# ft231x-breakout-v11.net
KiCad netlist of a schematic drawn in EAGLE
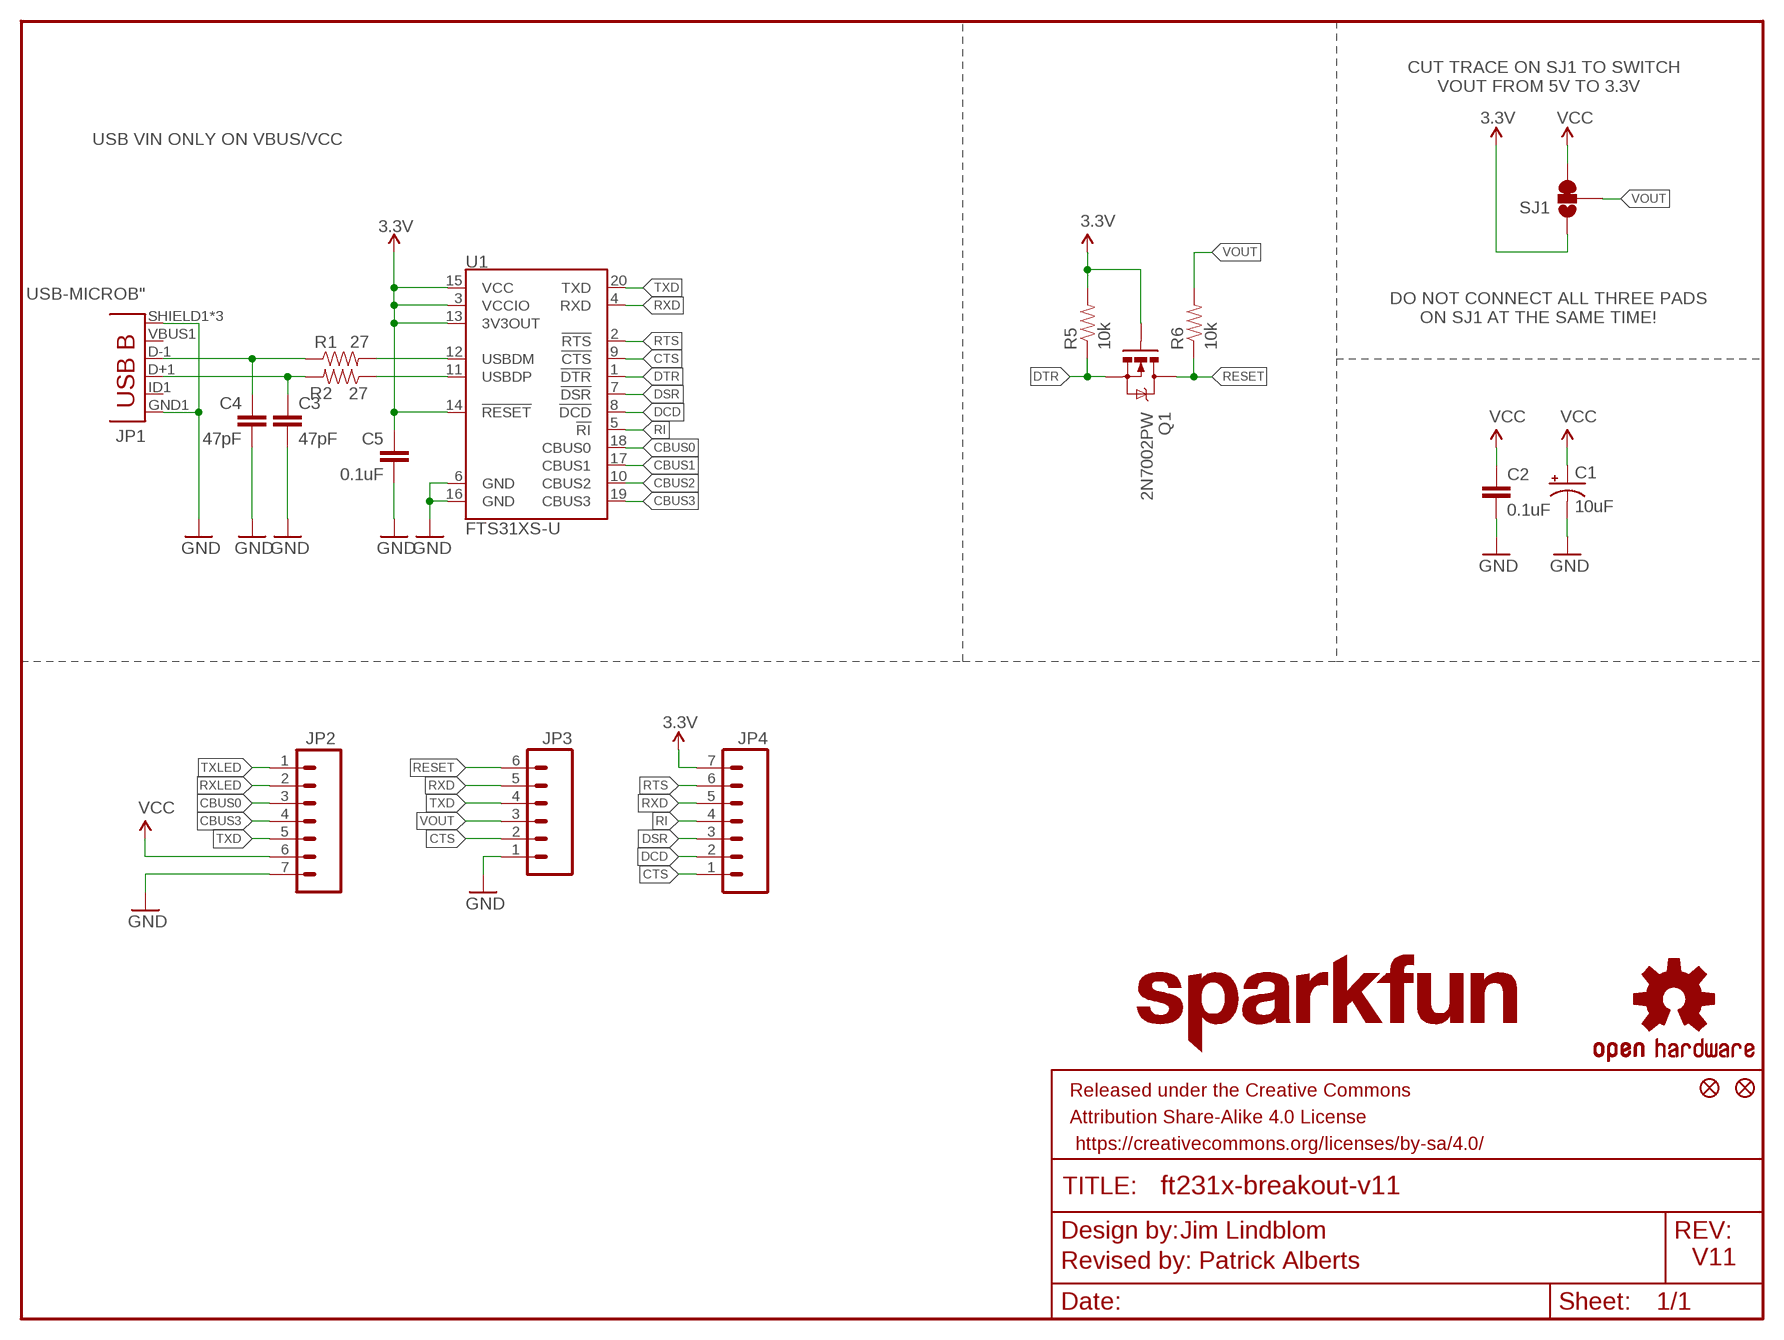
[diagram p0: schematic, sheet 1]

(export (version "E")
  (design (tool "Eeschema 10.0.6"))
  (components
    (comp (ref "C1")
      (value "10uF")
      (footprint "eagle-import:EIA3216")
      (libsource (lib "eagle-import") (part "10UF-16V-10%(TANT)"))
    )
    (comp (ref "C2")
      (value "0.1uF")
      (footprint "eagle-import:0603-CAP")
      (libsource (lib "eagle-import") (part "0.1UF-25V(+80/-20%)(0603)"))
    )
    (comp (ref "C3")
      (value "47pF")
      (footprint "eagle-import:0603-CAP")
      (libsource (lib "eagle-import") (part "47PF-50V-5%(0603)"))
    )
    (comp (ref "C4")
      (value "47pF")
      (footprint "eagle-import:0603-CAP")
      (libsource (lib "eagle-import") (part "47PF-50V-5%(0603)"))
    )
    (comp (ref "C5")
      (value "0.1uF")
      (footprint "eagle-import:0603-CAP")
      (libsource (lib "eagle-import") (part "0.1UF-25V(+80/-20%)(0603)"))
    )
    (comp (ref "FRAME1")
      (value "FRAME-LETTER")
      (footprint "eagle-import:CREATIVE_COMMONS")
      (libsource (lib "eagle-import") (part "FRAME-LETTER"))
    )
    (comp (ref "JP1")
      (value "USB-MICROB\"")
      (footprint "eagle-import:USB-B-MICRO-SMD_V03")
      (libsource (lib "eagle-import") (part "USB-MICROB{dblquote}"))
    )
    (comp (ref "JP2")
      (value "M07NO_SILK")
      (footprint "eagle-import:1X07_NO_SILK")
      (libsource (lib "eagle-import") (part "M07NO_SILK"))
    )
    (comp (ref "JP3")
      (value "M06NO_SILK_FEMALE_PTH")
      (footprint "eagle-import:1X06_NO_SILK")
      (libsource (lib "eagle-import") (part "M06NO_SILK_FEMALE_PTH"))
    )
    (comp (ref "JP4")
      (value "M07NO_SILK")
      (footprint "eagle-import:1X07_NO_SILK")
      (libsource (lib "eagle-import") (part "M07NO_SILK"))
    )
    (comp (ref "JP5")
      (value "FIDUCIAL1X2")
      (footprint "eagle-import:FIDUCIAL-1X2")
      (libsource (lib "eagle-import") (part "FIDUCIAL1X2"))
    )
    (comp (ref "JP6")
      (value "FIDUCIAL1X2")
      (footprint "eagle-import:FIDUCIAL-1X2")
      (libsource (lib "eagle-import") (part "FIDUCIAL1X2"))
    )
    (comp (ref "LOGO1")
      (value "SFE_LOGO_NAME.1_INCH")
      (footprint "eagle-import:SFE_LOGO_NAME_.1")
      (libsource (lib "eagle-import") (part "SFE_LOGO_NAME.1_INCH"))
    )
    (comp (ref "Q1")
      (value "2N7002PW")
      (footprint "eagle-import:SOT323")
      (libsource (lib "eagle-import") (part "MOSFET-NCHANNEL2N7002PW"))
    )
    (comp (ref "R1")
      (value "27")
      (footprint "eagle-import:0603-RES")
      (libsource (lib "eagle-import") (part "27OHM1/10W1%(0603)0603-RES"))
    )
    (comp (ref "R2")
      (value "27")
      (footprint "eagle-import:0603-RES")
      (libsource (lib "eagle-import") (part "27OHM1/10W1%(0603)0603-RES"))
    )
    (comp (ref "R5")
      (value "10k")
      (footprint "eagle-import:0603-RES@1")
      (libsource (lib "eagle-import") (part "10KOHM1/10W1%(0603)0603"))
    )
    (comp (ref "R6")
      (value "10k")
      (footprint "eagle-import:0603-RES@1")
      (libsource (lib "eagle-import") (part "10KOHM1/10W1%(0603)0603"))
    )
    (comp (ref "SJ1")
      (value "SOLDERJUMPER_2WAYS")
      (footprint "eagle-import:SJ_3")
      (libsource (lib "eagle-import") (part "SOLDERJUMPER_2WAYS"))
    )
    (comp (ref "U$1")
      (value "OSHW-LOGOS")
      (footprint "eagle-import:OSHW-LOGO-S")
      (libsource (lib "eagle-import") (part "OSHW-LOGOS"))
    )
    (comp (ref "U1")
      (value "FTS31XS-U")
      (footprint "eagle-import:SSOP20_L")
      (libsource (lib "eagle-import") (part "FT231XS"))
    )
  )
  (nets
    (net (code "1") (name "3.3V") (class "Default")
      (node (ref "C5") (pin "1") (pinfunction "1_1") (pintype "passive"))
      (node (ref "JP4") (pin "7") (pinfunction "7_7") (pintype "passive"))
      (node (ref "Q1") (pin "1") (pinfunction "G_1") (pintype "passive"))
      (node (ref "R5") (pin "2") (pinfunction "2_2") (pintype "passive"))
      (node (ref "SJ1") (pin "1") (pinfunction "1_1") (pintype "passive"))
      (node (ref "U1") (pin "13") (pinfunction "3V3OUT_13") (pintype "bidirectional"))
      (node (ref "U1") (pin "14") (pinfunction "~{RESET}_14") (pintype "bidirectional"))
      (node (ref "U1") (pin "15") (pinfunction "VCC_15") (pintype "bidirectional"))
      (node (ref "U1") (pin "3") (pinfunction "VCCIO_3") (pintype "bidirectional"))
    )
    (net (code "2") (name "CBUS0") (class "Default")
      (node (ref "JP2") (pin "3") (pinfunction "3_3") (pintype "passive"))
      (node (ref "U1") (pin "18") (pinfunction "CBUS0_18") (pintype "bidirectional"))
    )
    (net (code "3") (name "CBUS1") (class "Default")
      (node (ref "U1") (pin "17") (pinfunction "CBUS1_17") (pintype "bidirectional"))
    )
    (net (code "4") (name "CBUS2") (class "Default")
      (node (ref "U1") (pin "10") (pinfunction "CBUS2_10") (pintype "bidirectional"))
    )
    (net (code "5") (name "CBUS3") (class "Default")
      (node (ref "JP2") (pin "4") (pinfunction "4_4") (pintype "passive"))
      (node (ref "U1") (pin "19") (pinfunction "CBUS3_19") (pintype "bidirectional"))
    )
    (net (code "6") (name "CTS") (class "Default")
      (node (ref "JP3") (pin "2") (pinfunction "2_2") (pintype "passive"))
      (node (ref "JP4") (pin "1") (pinfunction "1_1") (pintype "passive"))
      (node (ref "U1") (pin "9") (pinfunction "~{CTS}_9") (pintype "bidirectional"))
    )
    (net (code "7") (name "DCD") (class "Default")
      (node (ref "JP4") (pin "2") (pinfunction "2_2") (pintype "passive"))
      (node (ref "U1") (pin "8") (pinfunction "~{DCD}_8") (pintype "bidirectional"))
    )
    (net (code "8") (name "DSR") (class "Default")
      (node (ref "JP4") (pin "3") (pinfunction "3_3") (pintype "passive"))
      (node (ref "U1") (pin "7") (pinfunction "~{DSR}_7") (pintype "bidirectional"))
    )
    (net (code "9") (name "DTR") (class "Default")
      (node (ref "Q1") (pin "2") (pinfunction "S_2") (pintype "passive"))
      (node (ref "R5") (pin "1") (pinfunction "1_1") (pintype "passive"))
      (node (ref "U1") (pin "1") (pinfunction "~{DTR}_1") (pintype "bidirectional"))
    )
    (net (code "10") (name "GND") (class "Default")
      (node (ref "C1") (pin "C") (pinfunction "-_C") (pintype "passive"))
      (node (ref "C2") (pin "2") (pinfunction "2_2") (pintype "passive"))
      (node (ref "C3") (pin "2") (pinfunction "2_2") (pintype "passive"))
      (node (ref "C4") (pin "2") (pinfunction "2_2") (pintype "passive"))
      (node (ref "C5") (pin "2") (pinfunction "2_2") (pintype "passive"))
      (node (ref "JP1") (pin "GND1") (pinfunction "GND_GND1") (pintype "bidirectional"))
      (node (ref "JP1") (pin "SHIELD1") (pinfunction "SHIELD_SHIELD1") (pintype "bidirectional"))
      (node (ref "JP1") (pin "SHIELD2") (pinfunction "SHIELD_SHIELD2") (pintype "bidirectional"))
      (node (ref "JP1") (pin "SHIELD3") (pinfunction "SHIELD_SHIELD3") (pintype "bidirectional"))
      (node (ref "JP2") (pin "7") (pinfunction "7_7") (pintype "passive"))
      (node (ref "JP3") (pin "1") (pinfunction "1_1") (pintype "passive"))
      (node (ref "U1") (pin "16") (pinfunction "GND_16") (pintype "bidirectional"))
      (node (ref "U1") (pin "6") (pinfunction "GND_6") (pintype "bidirectional"))
    )
    (net (code "11") (name "Net-(JP1-D+)") (class "Default")
      (node (ref "C3") (pin "1") (pinfunction "1_1") (pintype "passive"))
      (node (ref "JP1") (pin "D+1") (pinfunction "D+_D+1") (pintype "bidirectional"))
      (node (ref "R2") (pin "2") (pinfunction "2_2") (pintype "passive"))
    )
    (net (code "12") (name "Net-(JP1-D-)") (class "Default")
      (node (ref "C4") (pin "1") (pinfunction "1_1") (pintype "passive"))
      (node (ref "JP1") (pin "D-1") (pinfunction "D-_D-1") (pintype "bidirectional"))
      (node (ref "R1") (pin "1") (pinfunction "1_1") (pintype "passive"))
    )
    (net (code "13") (name "Net-(U1-USBDM)") (class "Default")
      (node (ref "R1") (pin "2") (pinfunction "2_2") (pintype "passive"))
      (node (ref "U1") (pin "12") (pinfunction "USBDM_12") (pintype "bidirectional"))
    )
    (net (code "14") (name "Net-(U1-USBDP)") (class "Default")
      (node (ref "R2") (pin "1") (pinfunction "1_1") (pintype "passive"))
      (node (ref "U1") (pin "11") (pinfunction "USBDP_11") (pintype "bidirectional"))
    )
    (net (code "15") (name "RESET") (class "Default")
      (node (ref "JP3") (pin "6") (pinfunction "6_6") (pintype "passive"))
      (node (ref "Q1") (pin "3") (pinfunction "D_3") (pintype "passive"))
      (node (ref "R6") (pin "1") (pinfunction "1_1") (pintype "passive"))
    )
    (net (code "16") (name "RI") (class "Default")
      (node (ref "JP4") (pin "4") (pinfunction "4_4") (pintype "passive"))
      (node (ref "U1") (pin "5") (pinfunction "~{RI}_5") (pintype "bidirectional"))
    )
    (net (code "17") (name "RTS") (class "Default")
      (node (ref "JP4") (pin "6") (pinfunction "6_6") (pintype "passive"))
      (node (ref "U1") (pin "2") (pinfunction "~{RTS}_2") (pintype "bidirectional"))
    )
    (net (code "18") (name "RXD") (class "Default")
      (node (ref "JP3") (pin "5") (pinfunction "5_5") (pintype "passive"))
      (node (ref "JP4") (pin "5") (pinfunction "5_5") (pintype "passive"))
      (node (ref "U1") (pin "4") (pinfunction "RXD_4") (pintype "bidirectional"))
    )
    (net (code "19") (name "RXLED") (class "Default")
      (node (ref "JP2") (pin "2") (pinfunction "2_2") (pintype "passive"))
    )
    (net (code "20") (name "TXD") (class "Default")
      (node (ref "JP2") (pin "5") (pinfunction "5_5") (pintype "passive"))
      (node (ref "JP3") (pin "4") (pinfunction "4_4") (pintype "passive"))
      (node (ref "U1") (pin "20") (pinfunction "TXD_20") (pintype "bidirectional"))
    )
    (net (code "21") (name "TXLED") (class "Default")
      (node (ref "JP2") (pin "1") (pinfunction "1_1") (pintype "passive"))
    )
    (net (code "22") (name "VCC") (class "Default")
      (node (ref "C1") (pin "A") (pinfunction "+_A") (pintype "passive"))
      (node (ref "C2") (pin "1") (pinfunction "1_1") (pintype "passive"))
      (node (ref "JP2") (pin "6") (pinfunction "6_6") (pintype "passive"))
      (node (ref "SJ1") (pin "3") (pinfunction "3_3") (pintype "passive"))
    )
    (net (code "23") (name "VOUT") (class "Default")
      (node (ref "JP3") (pin "3") (pinfunction "3_3") (pintype "passive"))
      (node (ref "R6") (pin "2") (pinfunction "2_2") (pintype "passive"))
      (node (ref "SJ1") (pin "2") (pinfunction "2_2") (pintype "passive"))
    )
    (net (code "24") (name "unconnected-(JP1-USBID-PadID1)") (class "Default")
      (node (ref "JP1") (pin "ID1") (pinfunction "USBID_ID1") (pintype "bidirectional"))
    )
    (net (code "25") (name "unconnected-(JP1-VBUS-PadVBUS1)") (class "Default")
      (node (ref "JP1") (pin "VBUS1") (pinfunction "VBUS_VBUS1") (pintype "bidirectional"))
    )
  )
)
